# ProPrj_51board_2024-12-12.net
KiCad netlist of a schematic drawn in EasyEDA Pro
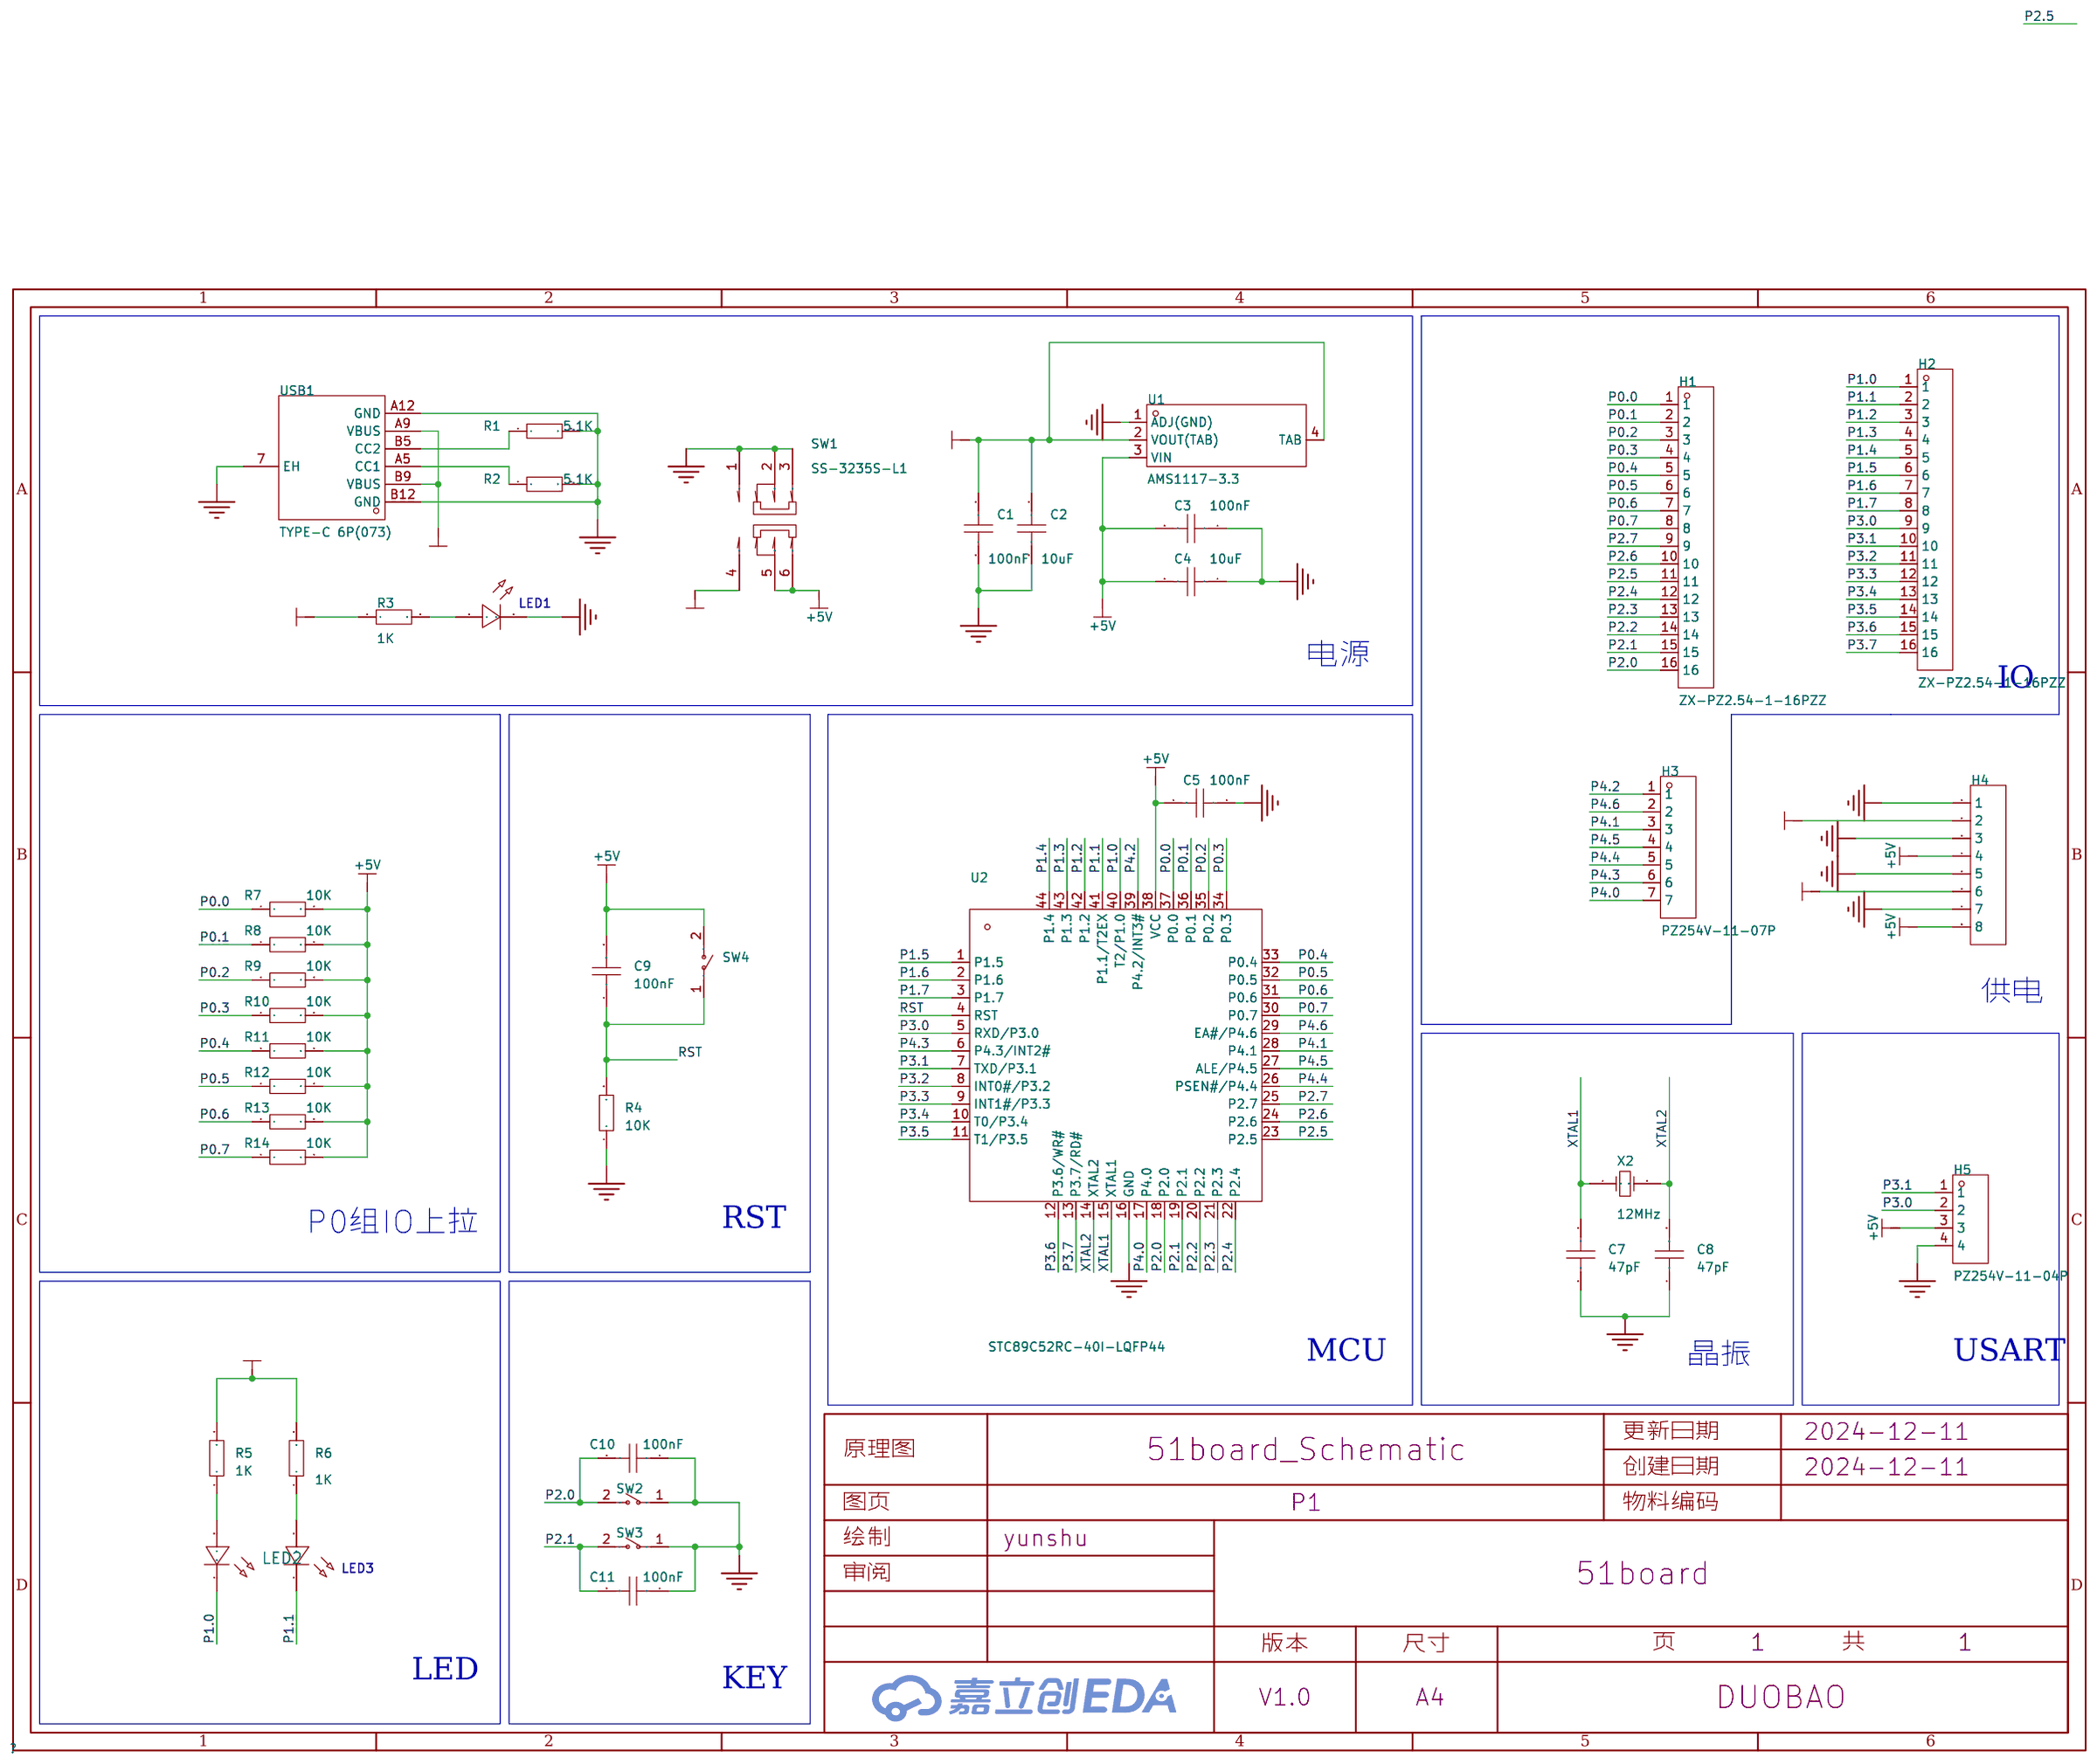
[diagram p0: schematic sheet]

(export (version "E")
  (design (tool "Eeschema 10.0.6"))
  (components
    (comp (ref "C1")
      (value "100nF")
      (footprint "easyedapro:C0603")
      (libsource (lib "easyedapro") (part "CapAcitance"))
    )
    (comp (ref "C2")
      (value "10uF")
      (footprint "easyedapro:C0603")
      (libsource (lib "easyedapro") (part "CapAcitance"))
    )
    (comp (ref "C3")
      (value "100nF")
      (footprint "easyedapro:C0603")
      (libsource (lib "easyedapro") (part "CapAcitance"))
    )
    (comp (ref "C4")
      (value "10uF")
      (footprint "easyedapro:C0603")
      (libsource (lib "easyedapro") (part "CapAcitance"))
    )
    (comp (ref "C5")
      (value "100nF")
      (footprint "easyedapro:C0603")
      (libsource (lib "easyedapro") (part "CapAcitance"))
    )
    (comp (ref "C7")
      (value "47pF")
      (footprint "easyedapro:C0603")
      (libsource (lib "easyedapro") (part "CapAcitance"))
    )
    (comp (ref "C8")
      (value "47pF")
      (footprint "easyedapro:C0603")
      (libsource (lib "easyedapro") (part "CapAcitance"))
    )
    (comp (ref "C9")
      (value "100nF")
      (footprint "easyedapro:C0603")
      (libsource (lib "easyedapro") (part "CapAcitance"))
    )
    (comp (ref "C10")
      (value "100nF")
      (footprint "easyedapro:C0603")
      (libsource (lib "easyedapro") (part "CapAcitance"))
    )
    (comp (ref "C11")
      (value "100nF")
      (footprint "easyedapro:C0603")
      (libsource (lib "easyedapro") (part "CapAcitance"))
    )
    (comp (ref "H1")
      (value "ZX-PZ2.54-1-16PZZ")
      (footprint "easyedapro:HDR-TH_16P-P2.54-V-M")
      (fields (field (name "Manufacturer") "Megastar(兆星)"))
      (libsource (lib "easyedapro") (part "HDR_2.54-1x16P"))
    )
    (comp (ref "H2")
      (value "ZX-PZ2.54-1-16PZZ")
      (footprint "easyedapro:HDR-TH_16P-P2.54-V-M")
      (fields (field (name "Manufacturer") "Megastar(兆星)"))
      (libsource (lib "easyedapro") (part "HDR_2.54-1x16P"))
    )
    (comp (ref "H3")
      (value "PZ254V-11-07P")
      (footprint "easyedapro:HDR-TH_7P-P2.54-V-M")
      (fields (field (name "Manufacturer") "XFCN(兴飞)"))
      (libsource (lib "easyedapro") (part "PZ254V-11-07P"))
    )
    (comp (ref "H4")
      (value "~")
      (footprint "easyedapro:HDR-TH_8P-P2.54-V-F-1")
      (libsource (lib "easyedapro") (part "Header-Female-2.54_1x8"))
    )
    (comp (ref "H5")
      (value "PZ254V-11-04P")
      (footprint "easyedapro:HDR-TH_4P-P2.54-V-M")
      (fields (field (name "Manufacturer") "XFCN(兴飞)"))
      (libsource (lib "easyedapro") (part "PZ254V-11-04P"))
    )
    (comp (ref "LED1")
      (value "~")
      (footprint "easyedapro:LED_0805")
      (libsource (lib "easyedapro") (part "LED_G"))
    )
    (comp (ref "LED2")
      (value "~")
      (footprint "easyedapro:LED_0805")
      (libsource (lib "easyedapro") (part "LED_R"))
    )
    (comp (ref "LED3")
      (value "~")
      (footprint "easyedapro:LED_0805")
      (libsource (lib "easyedapro") (part "LED_B"))
    )
    (comp (ref "R1") (value "5.1K") (footprint "easyedapro:R0805") (libsource (lib "easyedapro") (part "电阻")))
    (comp (ref "R2") (value "5.1K") (footprint "easyedapro:R0805") (libsource (lib "easyedapro") (part "电阻")))
    (comp (ref "R3") (value "1K") (footprint "easyedapro:R0805") (libsource (lib "easyedapro") (part "电阻")))
    (comp (ref "R4") (value "10K") (footprint "easyedapro:R0805") (libsource (lib "easyedapro") (part "电阻")))
    (comp (ref "R5") (value "1K") (footprint "easyedapro:R0805") (libsource (lib "easyedapro") (part "电阻")))
    (comp (ref "R6") (value "1K") (footprint "easyedapro:R0805") (libsource (lib "easyedapro") (part "电阻")))
    (comp (ref "R7") (value "10K") (footprint "easyedapro:R0805") (libsource (lib "easyedapro") (part "电阻")))
    (comp (ref "R8") (value "10K") (footprint "easyedapro:R0805") (libsource (lib "easyedapro") (part "电阻")))
    (comp (ref "R9") (value "10K") (footprint "easyedapro:R0805") (libsource (lib "easyedapro") (part "电阻")))
    (comp (ref "R10") (value "10K") (footprint "easyedapro:R0805") (libsource (lib "easyedapro") (part "电阻")))
    (comp (ref "R11") (value "10K") (footprint "easyedapro:R0805") (libsource (lib "easyedapro") (part "电阻")))
    (comp (ref "R12") (value "10K") (footprint "easyedapro:R0805") (libsource (lib "easyedapro") (part "电阻")))
    (comp (ref "R13") (value "10K") (footprint "easyedapro:R0805") (libsource (lib "easyedapro") (part "电阻")))
    (comp (ref "R14") (value "10K") (footprint "easyedapro:R0805") (libsource (lib "easyedapro") (part "电阻")))
    (comp (ref "SW1")
      (value "SS-3235S-L1")
      (footprint "easyedapro:SW-SMD_SS-3235S-LX")
      (description "电路结构:双刀双掷;安装方式:卧贴;开关颜色:黑色;额定电流(DC):50mA;额定电压(DC):12V;额定电流(AC):50mA;额定电压(AC):12V;机械寿命:1万次;")
      (fields (field (name "Manufacturer") "XKB Connectivity(中国星坤)"))
      (libsource (lib "easyedapro") (part "SS-3235S-L1"))
    )
    (comp (ref "SW2")
      (value "轻触按键 3x6x2.5mm")
      (footprint "easyedapro:SW-SMD_L6.1-W3.7-LS8.0")
      (description "开关长度:6.05mm;开关宽度:3.65mm;开关高度:2.5mm;机械寿命:-;")
      (fields (field (name "Manufacturer") "BBJ"))
      (libsource (lib "easyedapro") (part "轻触按键 3X6X2.5MM"))
    )
    (comp (ref "SW3")
      (value "轻触按键 3x6x2.5mm")
      (footprint "easyedapro:SW-SMD_L6.1-W3.7-LS8.0")
      (description "开关长度:6.05mm;开关宽度:3.65mm;开关高度:2.5mm;机械寿命:-;")
      (fields (field (name "Manufacturer") "BBJ"))
      (libsource (lib "easyedapro") (part "轻触按键 3X6X2.5MM"))
    )
    (comp (ref "SW4")
      (value "轻触按键 3x6x2.5mm")
      (footprint "easyedapro:SW-SMD_L6.1-W3.7-LS8.0")
      (description "开关长度:6.05mm;开关宽度:3.65mm;开关高度:2.5mm;机械寿命:-;")
      (fields (field (name "Manufacturer") "BBJ"))
      (libsource (lib "easyedapro") (part "轻触按键 3X6X2.5MM"))
    )
    (comp (ref "U1")
      (value "AMS1117-3.3")
      (footprint "easyedapro:SOT-223-4_L6.5-W3.5-P2.30-LS7.0-BR")
      (description "输出类型:固定;最大输入电压:18V;输出电压:3.3V;输出电流:1A;电源纹波抑制比(PSRR):60dB@(120Hz);输出极性:正极;")
      (fields (field (name "Manufacturer") "UMW(友台半导体)"))
      (libsource (lib "easyedapro") (part "AMS1117-3.3_C347222"))
    )
    (comp (ref "U2")
      (value "STC89C52RC-40I-LQFP44")
      (footprint "easyedapro:LQFP-44_L10.0-W10.0-P0.80-LS12.0-BL")
      (description "CPU内核:51系列;程序存储容量:8KB;RAM总容量:512Byte;GPIO端口数量:39;工作电压范围:3.3V~5.5V;CPU最大主频:-;程序存储器类型:FLASH;")
      (fields (field (name "Manufacturer") "STC(宏晶)"))
      (libsource (lib "easyedapro") (part "STC89C52RC-40I_C8707"))
    )
    (comp (ref "USB1")
      (value "TYPE-C 6P(073)")
      (footprint "easyedapro:TYPE-C-SMD_TYPE-C-6P_5")
      (description "连接器类型:Type-C;标准:USB 3.1;公母:母;安装方式:卧贴;触点数量:6P;端口数量:1;额定电流 - 电源:3A;工作温度范围:-25°C~+85°C;")
      (fields (field (name "Manufacturer") "SHOU HAN(首韩)"))
      (libsource (lib "easyedapro") (part "TYPE-C 6P(073)"))
    )
    (comp (ref "X2")
      (value "12MHz")
      (footprint "easyedapro:OSC-TH_BD2.0-P0.50")
      (description "晶振类型:直插晶振;频率:12MHz;常温频差:±20ppm;外接负载电容:20pF;频率稳定度(全温):±30ppm;")
      (fields
        (field (name "Manufacturer Part") "TXD12M0002206LDBEO00S")
        (field (name "Manufacturer") "YJX(雅晶鑫)")
      )
      (libsource (lib "easyedapro") (part "TXD12M0002206LDBEO00S"))
    )
  )
  (nets
    (net (code "1") (name "+5V") (class "Default")
      (node (ref "C3") (pin "2") (pinfunction "2_2") (pintype "input"))
      (node (ref "C4") (pin "2") (pinfunction "2_2") (pintype "input"))
      (node (ref "C5") (pin "1") (pinfunction "1_1") (pintype "input"))
      (node (ref "C9") (pin "2") (pinfunction "2_2") (pintype "input"))
      (node (ref "H4") (pin "4") (pinfunction "4_4") (pintype "input"))
      (node (ref "H4") (pin "8") (pinfunction "8_8") (pintype "input"))
      (node (ref "H5") (pin "3") (pinfunction "3_3") (pintype "unspecified"))
      (node (ref "R10") (pin "2") (pinfunction "2_2") (pintype "input"))
      (node (ref "R11") (pin "2") (pinfunction "2_2") (pintype "input"))
      (node (ref "R12") (pin "2") (pinfunction "2_2") (pintype "input"))
      (node (ref "R13") (pin "2") (pinfunction "2_2") (pintype "input"))
      (node (ref "R14") (pin "2") (pinfunction "2_2") (pintype "input"))
      (node (ref "R7") (pin "2") (pinfunction "2_2") (pintype "input"))
      (node (ref "R8") (pin "2") (pinfunction "2_2") (pintype "input"))
      (node (ref "R9") (pin "2") (pinfunction "2_2") (pintype "input"))
      (node (ref "SW1") (pin "5") (pinfunction "5_5") (pintype "unspecified"))
      (node (ref "SW1") (pin "6") (pinfunction "6_6") (pintype "unspecified"))
      (node (ref "SW4") (pin "2") (pinfunction "2_2") (pintype "unspecified"))
      (node (ref "U1") (pin "3") (pinfunction "VIN_3") (pintype "unspecified"))
      (node (ref "U2") (pin "38") (pinfunction "VCC_38") (pintype "unspecified"))
    )
    (net (code "2") (name "/P0.0") (class "Default")
      (node (ref "H1") (pin "1") (pinfunction "1_1") (pintype "input"))
      (node (ref "R7") (pin "1") (pinfunction "1_1") (pintype "input"))
      (node (ref "U2") (pin "37") (pinfunction "P0.0_37") (pintype "unspecified"))
    )
    (net (code "3") (name "/P0.1") (class "Default")
      (node (ref "H1") (pin "2") (pinfunction "2_2") (pintype "input"))
      (node (ref "R8") (pin "1") (pinfunction "1_1") (pintype "input"))
      (node (ref "U2") (pin "36") (pinfunction "P0.1_36") (pintype "unspecified"))
    )
    (net (code "4") (name "/P0.2") (class "Default")
      (node (ref "H1") (pin "3") (pinfunction "3_3") (pintype "input"))
      (node (ref "R9") (pin "1") (pinfunction "1_1") (pintype "input"))
      (node (ref "U2") (pin "35") (pinfunction "P0.2_35") (pintype "unspecified"))
    )
    (net (code "5") (name "/P0.3") (class "Default")
      (node (ref "H1") (pin "4") (pinfunction "4_4") (pintype "input"))
      (node (ref "R10") (pin "1") (pinfunction "1_1") (pintype "input"))
      (node (ref "U2") (pin "34") (pinfunction "P0.3_34") (pintype "unspecified"))
    )
    (net (code "6") (name "/P0.4") (class "Default")
      (node (ref "H1") (pin "5") (pinfunction "5_5") (pintype "input"))
      (node (ref "R11") (pin "1") (pinfunction "1_1") (pintype "input"))
      (node (ref "U2") (pin "33") (pinfunction "P0.4_33") (pintype "unspecified"))
    )
    (net (code "7") (name "/P0.5") (class "Default")
      (node (ref "H1") (pin "6") (pinfunction "6_6") (pintype "input"))
      (node (ref "R12") (pin "1") (pinfunction "1_1") (pintype "input"))
      (node (ref "U2") (pin "32") (pinfunction "P0.5_32") (pintype "unspecified"))
    )
    (net (code "8") (name "/P0.6") (class "Default")
      (node (ref "H1") (pin "7") (pinfunction "7_7") (pintype "input"))
      (node (ref "R13") (pin "1") (pinfunction "1_1") (pintype "input"))
      (node (ref "U2") (pin "31") (pinfunction "P0.6_31") (pintype "unspecified"))
    )
    (net (code "9") (name "/P0.7") (class "Default")
      (node (ref "H1") (pin "8") (pinfunction "8_8") (pintype "input"))
      (node (ref "R14") (pin "1") (pinfunction "1_1") (pintype "input"))
      (node (ref "U2") (pin "30") (pinfunction "P0.7_30") (pintype "unspecified"))
    )
    (net (code "10") (name "/P1.0") (class "Default")
      (node (ref "H2") (pin "1") (pinfunction "1_1") (pintype "input"))
      (node (ref "LED2") (pin "1") (pinfunction "C_1") (pintype "input"))
      (node (ref "U2") (pin "40") (pinfunction "T2/P1.0_40") (pintype "unspecified"))
    )
    (net (code "11") (name "/P1.1") (class "Default")
      (node (ref "H2") (pin "2") (pinfunction "2_2") (pintype "input"))
      (node (ref "LED3") (pin "1") (pinfunction "C_1") (pintype "input"))
      (node (ref "U2") (pin "41") (pinfunction "P1.1/T2EX_41") (pintype "unspecified"))
    )
    (net (code "12") (name "/P1.2") (class "Default")
      (node (ref "H2") (pin "3") (pinfunction "3_3") (pintype "input"))
      (node (ref "U2") (pin "42") (pinfunction "P1.2_42") (pintype "unspecified"))
    )
    (net (code "13") (name "/P1.3") (class "Default")
      (node (ref "H2") (pin "4") (pinfunction "4_4") (pintype "input"))
      (node (ref "U2") (pin "43") (pinfunction "P1.3_43") (pintype "unspecified"))
    )
    (net (code "14") (name "/P1.4") (class "Default")
      (node (ref "H2") (pin "5") (pinfunction "5_5") (pintype "input"))
      (node (ref "U2") (pin "44") (pinfunction "P1.4_44") (pintype "unspecified"))
    )
    (net (code "15") (name "/P1.5") (class "Default")
      (node (ref "H2") (pin "6") (pinfunction "6_6") (pintype "input"))
      (node (ref "U2") (pin "1") (pinfunction "P1.5_1") (pintype "unspecified"))
    )
    (net (code "16") (name "/P1.6") (class "Default")
      (node (ref "H2") (pin "7") (pinfunction "7_7") (pintype "input"))
      (node (ref "U2") (pin "2") (pinfunction "P1.6_2") (pintype "unspecified"))
    )
    (net (code "17") (name "/P1.7") (class "Default")
      (node (ref "H2") (pin "8") (pinfunction "8_8") (pintype "input"))
      (node (ref "U2") (pin "3") (pinfunction "P1.7_3") (pintype "unspecified"))
    )
    (net (code "18") (name "/P2.0") (class "Default")
      (node (ref "C10") (pin "2") (pinfunction "2_2") (pintype "input"))
      (node (ref "H1") (pin "16") (pinfunction "16_16") (pintype "input"))
      (node (ref "SW2") (pin "2") (pinfunction "2_2") (pintype "unspecified"))
      (node (ref "U2") (pin "18") (pinfunction "P2.0_18") (pintype "unspecified"))
    )
    (net (code "19") (name "/P2.1") (class "Default")
      (node (ref "C11") (pin "2") (pinfunction "2_2") (pintype "input"))
      (node (ref "H1") (pin "15") (pinfunction "15_15") (pintype "input"))
      (node (ref "SW3") (pin "2") (pinfunction "2_2") (pintype "unspecified"))
      (node (ref "U2") (pin "19") (pinfunction "P2.1_19") (pintype "unspecified"))
    )
    (net (code "20") (name "/P2.2") (class "Default")
      (node (ref "H1") (pin "14") (pinfunction "14_14") (pintype "input"))
      (node (ref "U2") (pin "20") (pinfunction "P2.2_20") (pintype "unspecified"))
    )
    (net (code "21") (name "/P2.3") (class "Default")
      (node (ref "H1") (pin "13") (pinfunction "13_13") (pintype "input"))
      (node (ref "U2") (pin "21") (pinfunction "P2.3_21") (pintype "unspecified"))
    )
    (net (code "22") (name "/P2.4") (class "Default")
      (node (ref "H1") (pin "12") (pinfunction "12_12") (pintype "input"))
      (node (ref "U2") (pin "22") (pinfunction "P2.4_22") (pintype "unspecified"))
    )
    (net (code "23") (name "/P2.5") (class "Default")
      (node (ref "H1") (pin "11") (pinfunction "11_11") (pintype "input"))
      (node (ref "U2") (pin "23") (pinfunction "P2.5_23") (pintype "unspecified"))
    )
    (net (code "24") (name "/P2.6") (class "Default")
      (node (ref "H1") (pin "10") (pinfunction "10_10") (pintype "input"))
      (node (ref "U2") (pin "24") (pinfunction "P2.6_24") (pintype "unspecified"))
    )
    (net (code "25") (name "/P2.7") (class "Default")
      (node (ref "H1") (pin "9") (pinfunction "9_9") (pintype "input"))
      (node (ref "U2") (pin "25") (pinfunction "P2.7_25") (pintype "unspecified"))
    )
    (net (code "26") (name "/P3.0") (class "Default")
      (node (ref "H2") (pin "9") (pinfunction "9_9") (pintype "input"))
      (node (ref "H5") (pin "2") (pinfunction "2_2") (pintype "unspecified"))
      (node (ref "U2") (pin "5") (pinfunction "RXD/P3.0_5") (pintype "unspecified"))
    )
    (net (code "27") (name "/P3.1") (class "Default")
      (node (ref "H2") (pin "10") (pinfunction "10_10") (pintype "input"))
      (node (ref "H5") (pin "1") (pinfunction "1_1") (pintype "unspecified"))
      (node (ref "U2") (pin "7") (pinfunction "TXD/P3.1_7") (pintype "unspecified"))
    )
    (net (code "28") (name "/P3.2") (class "Default")
      (node (ref "H2") (pin "11") (pinfunction "11_11") (pintype "input"))
      (node (ref "U2") (pin "8") (pinfunction "INT0#/P3.2_8") (pintype "unspecified"))
    )
    (net (code "29") (name "/P3.3") (class "Default")
      (node (ref "H2") (pin "12") (pinfunction "12_12") (pintype "input"))
      (node (ref "U2") (pin "9") (pinfunction "INT1#/P3.3_9") (pintype "unspecified"))
    )
    (net (code "30") (name "/P3.4") (class "Default")
      (node (ref "H2") (pin "13") (pinfunction "13_13") (pintype "input"))
      (node (ref "U2") (pin "10") (pinfunction "T0/P3.4_10") (pintype "unspecified"))
    )
    (net (code "31") (name "/P3.5") (class "Default")
      (node (ref "H2") (pin "14") (pinfunction "14_14") (pintype "input"))
      (node (ref "U2") (pin "11") (pinfunction "T1/P3.5_11") (pintype "unspecified"))
    )
    (net (code "32") (name "/P3.6") (class "Default")
      (node (ref "H2") (pin "15") (pinfunction "15_15") (pintype "input"))
      (node (ref "U2") (pin "12") (pinfunction "P3.6/WR#_12") (pintype "unspecified"))
    )
    (net (code "33") (name "/P3.7") (class "Default")
      (node (ref "H2") (pin "16") (pinfunction "16_16") (pintype "input"))
      (node (ref "U2") (pin "13") (pinfunction "P3.7/RD#_13") (pintype "unspecified"))
    )
    (net (code "34") (name "/P4.0") (class "Default")
      (node (ref "H3") (pin "7") (pinfunction "7_7") (pintype "unspecified"))
      (node (ref "U2") (pin "17") (pinfunction "P4.0_17") (pintype "unspecified"))
    )
    (net (code "35") (name "/P4.1") (class "Default")
      (node (ref "H3") (pin "3") (pinfunction "3_3") (pintype "unspecified"))
      (node (ref "U2") (pin "28") (pinfunction "P4.1_28") (pintype "unspecified"))
    )
    (net (code "36") (name "/P4.2") (class "Default")
      (node (ref "H3") (pin "1") (pinfunction "1_1") (pintype "unspecified"))
      (node (ref "U2") (pin "39") (pinfunction "P4.2/INT3#_39") (pintype "unspecified"))
    )
    (net (code "37") (name "/P4.3") (class "Default")
      (node (ref "H3") (pin "6") (pinfunction "6_6") (pintype "unspecified"))
      (node (ref "U2") (pin "6") (pinfunction "P4.3/INT2#_6") (pintype "unspecified"))
    )
    (net (code "38") (name "/P4.4") (class "Default")
      (node (ref "H3") (pin "5") (pinfunction "5_5") (pintype "unspecified"))
      (node (ref "U2") (pin "26") (pinfunction "PSEN#/P4.4_26") (pintype "unspecified"))
    )
    (net (code "39") (name "/P4.5") (class "Default")
      (node (ref "H3") (pin "4") (pinfunction "4_4") (pintype "unspecified"))
      (node (ref "U2") (pin "27") (pinfunction "ALE/P4.5_27") (pintype "unspecified"))
    )
    (net (code "40") (name "/P4.6") (class "Default")
      (node (ref "H3") (pin "2") (pinfunction "2_2") (pintype "unspecified"))
      (node (ref "U2") (pin "29") (pinfunction "EA#/P4.6_29") (pintype "unspecified"))
    )
    (net (code "41") (name "/RST") (class "Default")
      (node (ref "C9") (pin "1") (pinfunction "1_1") (pintype "input"))
      (node (ref "R4") (pin "2") (pinfunction "2_2") (pintype "input"))
      (node (ref "SW4") (pin "1") (pinfunction "1_1") (pintype "unspecified"))
      (node (ref "U2") (pin "4") (pinfunction "RST_4") (pintype "unspecified"))
    )
    (net (code "42") (name "/XTAL1") (class "Default")
      (node (ref "C7") (pin "2") (pinfunction "2_2") (pintype "input"))
      (node (ref "U2") (pin "15") (pinfunction "XTAL1_15") (pintype "unspecified"))
      (node (ref "X2") (pin "1") (pinfunction "OSC1_1") (pintype "unspecified"))
    )
    (net (code "43") (name "/XTAL2") (class "Default")
      (node (ref "C8") (pin "2") (pinfunction "2_2") (pintype "input"))
      (node (ref "U2") (pin "14") (pinfunction "XTAL2_14") (pintype "unspecified"))
      (node (ref "X2") (pin "2") (pinfunction "OSC2_2") (pintype "unspecified"))
    )
    (net (code "44") (name "GND") (class "Default")
      (node (ref "C1") (pin "2") (pinfunction "2_2") (pintype "input"))
      (node (ref "C10") (pin "1") (pinfunction "1_1") (pintype "input"))
      (node (ref "C11") (pin "1") (pinfunction "1_1") (pintype "input"))
      (node (ref "C2") (pin "2") (pinfunction "2_2") (pintype "input"))
      (node (ref "C3") (pin "1") (pinfunction "1_1") (pintype "input"))
      (node (ref "C4") (pin "1") (pinfunction "1_1") (pintype "input"))
      (node (ref "C5") (pin "2") (pinfunction "2_2") (pintype "input"))
      (node (ref "C7") (pin "1") (pinfunction "1_1") (pintype "input"))
      (node (ref "C8") (pin "1") (pinfunction "1_1") (pintype "input"))
      (node (ref "H4") (pin "1") (pinfunction "1_1") (pintype "input"))
      (node (ref "H4") (pin "3") (pinfunction "3_3") (pintype "input"))
      (node (ref "H4") (pin "5") (pinfunction "5_5") (pintype "input"))
      (node (ref "H4") (pin "7") (pinfunction "7_7") (pintype "input"))
      (node (ref "H5") (pin "4") (pinfunction "4_4") (pintype "unspecified"))
      (node (ref "LED1") (pin "1") (pinfunction "C_1") (pintype "input"))
      (node (ref "R1") (pin "2") (pinfunction "2_2") (pintype "input"))
      (node (ref "R2") (pin "2") (pinfunction "2_2") (pintype "input"))
      (node (ref "R4") (pin "1") (pinfunction "1_1") (pintype "input"))
      (node (ref "SW1") (pin "1") (pinfunction "1_1") (pintype "unspecified"))
      (node (ref "SW1") (pin "2") (pinfunction "2_2") (pintype "unspecified"))
      (node (ref "SW1") (pin "3") (pinfunction "3_3") (pintype "unspecified"))
      (node (ref "SW2") (pin "1") (pinfunction "1_1") (pintype "unspecified"))
      (node (ref "SW3") (pin "1") (pinfunction "1_1") (pintype "unspecified"))
      (node (ref "U1") (pin "1") (pinfunction "ADJ(GND)_1") (pintype "unspecified"))
      (node (ref "U2") (pin "16") (pinfunction "GND_16") (pintype "unspecified"))
      (node (ref "USB1") (pin "7") (pinfunction "EH_7") (pintype "unspecified"))
      (node (ref "USB1") (pin "A12") (pinfunction "GND_A12") (pintype "unspecified"))
      (node (ref "USB1") (pin "B12") (pinfunction "GND_B12") (pintype "unspecified"))
    )
    (net (code "45") (name "Net-(LED1-A)") (class "Default")
      (node (ref "LED1") (pin "2") (pinfunction "A_2") (pintype "input"))
      (node (ref "R3") (pin "2") (pinfunction "2_2") (pintype "input"))
    )
    (net (code "46") (name "Net-(LED2-A)") (class "Default")
      (node (ref "LED2") (pin "2") (pinfunction "A_2") (pintype "input"))
      (node (ref "R5") (pin "1") (pinfunction "1_1") (pintype "input"))
    )
    (net (code "47") (name "Net-(LED3-A)") (class "Default")
      (node (ref "LED3") (pin "2") (pinfunction "A_2") (pintype "input"))
      (node (ref "R6") (pin "1") (pinfunction "1_1") (pintype "input"))
    )
    (net (code "48") (name "Net-(USB1-CC1)") (class "Default")
      (node (ref "R2") (pin "1") (pinfunction "1_1") (pintype "input"))
      (node (ref "USB1") (pin "A5") (pinfunction "CC1_A5") (pintype "unspecified"))
    )
    (net (code "49") (name "Net-(USB1-CC2)") (class "Default")
      (node (ref "R1") (pin "1") (pinfunction "1_1") (pintype "input"))
      (node (ref "USB1") (pin "B5") (pinfunction "CC2_B5") (pintype "unspecified"))
    )
    (net (code "50") (name "VCC+3.3V") (class "Default")
      (node (ref "C1") (pin "1") (pinfunction "1_1") (pintype "input"))
      (node (ref "C2") (pin "1") (pinfunction "1_1") (pintype "input"))
      (node (ref "H4") (pin "2") (pinfunction "2_2") (pintype "input"))
      (node (ref "H4") (pin "6") (pinfunction "6_6") (pintype "input"))
      (node (ref "R3") (pin "1") (pinfunction "1_1") (pintype "input"))
      (node (ref "R5") (pin "2") (pinfunction "2_2") (pintype "input"))
      (node (ref "R6") (pin "2") (pinfunction "2_2") (pintype "input"))
      (node (ref "U1") (pin "2") (pinfunction "VOUT(TAB)_2") (pintype "unspecified"))
      (node (ref "U1") (pin "4") (pinfunction "TAB_4") (pintype "unspecified"))
    )
    (net (code "51") (name "VCC+5V") (class "Default")
      (node (ref "SW1") (pin "4") (pinfunction "4_4") (pintype "unspecified"))
      (node (ref "USB1") (pin "A9") (pinfunction "VBUS_A9") (pintype "unspecified"))
      (node (ref "USB1") (pin "B9") (pinfunction "VBUS_B9") (pintype "unspecified"))
    )
  )
)
